# mysch.net
KiCad netlist of a schematic drawn in EAGLE
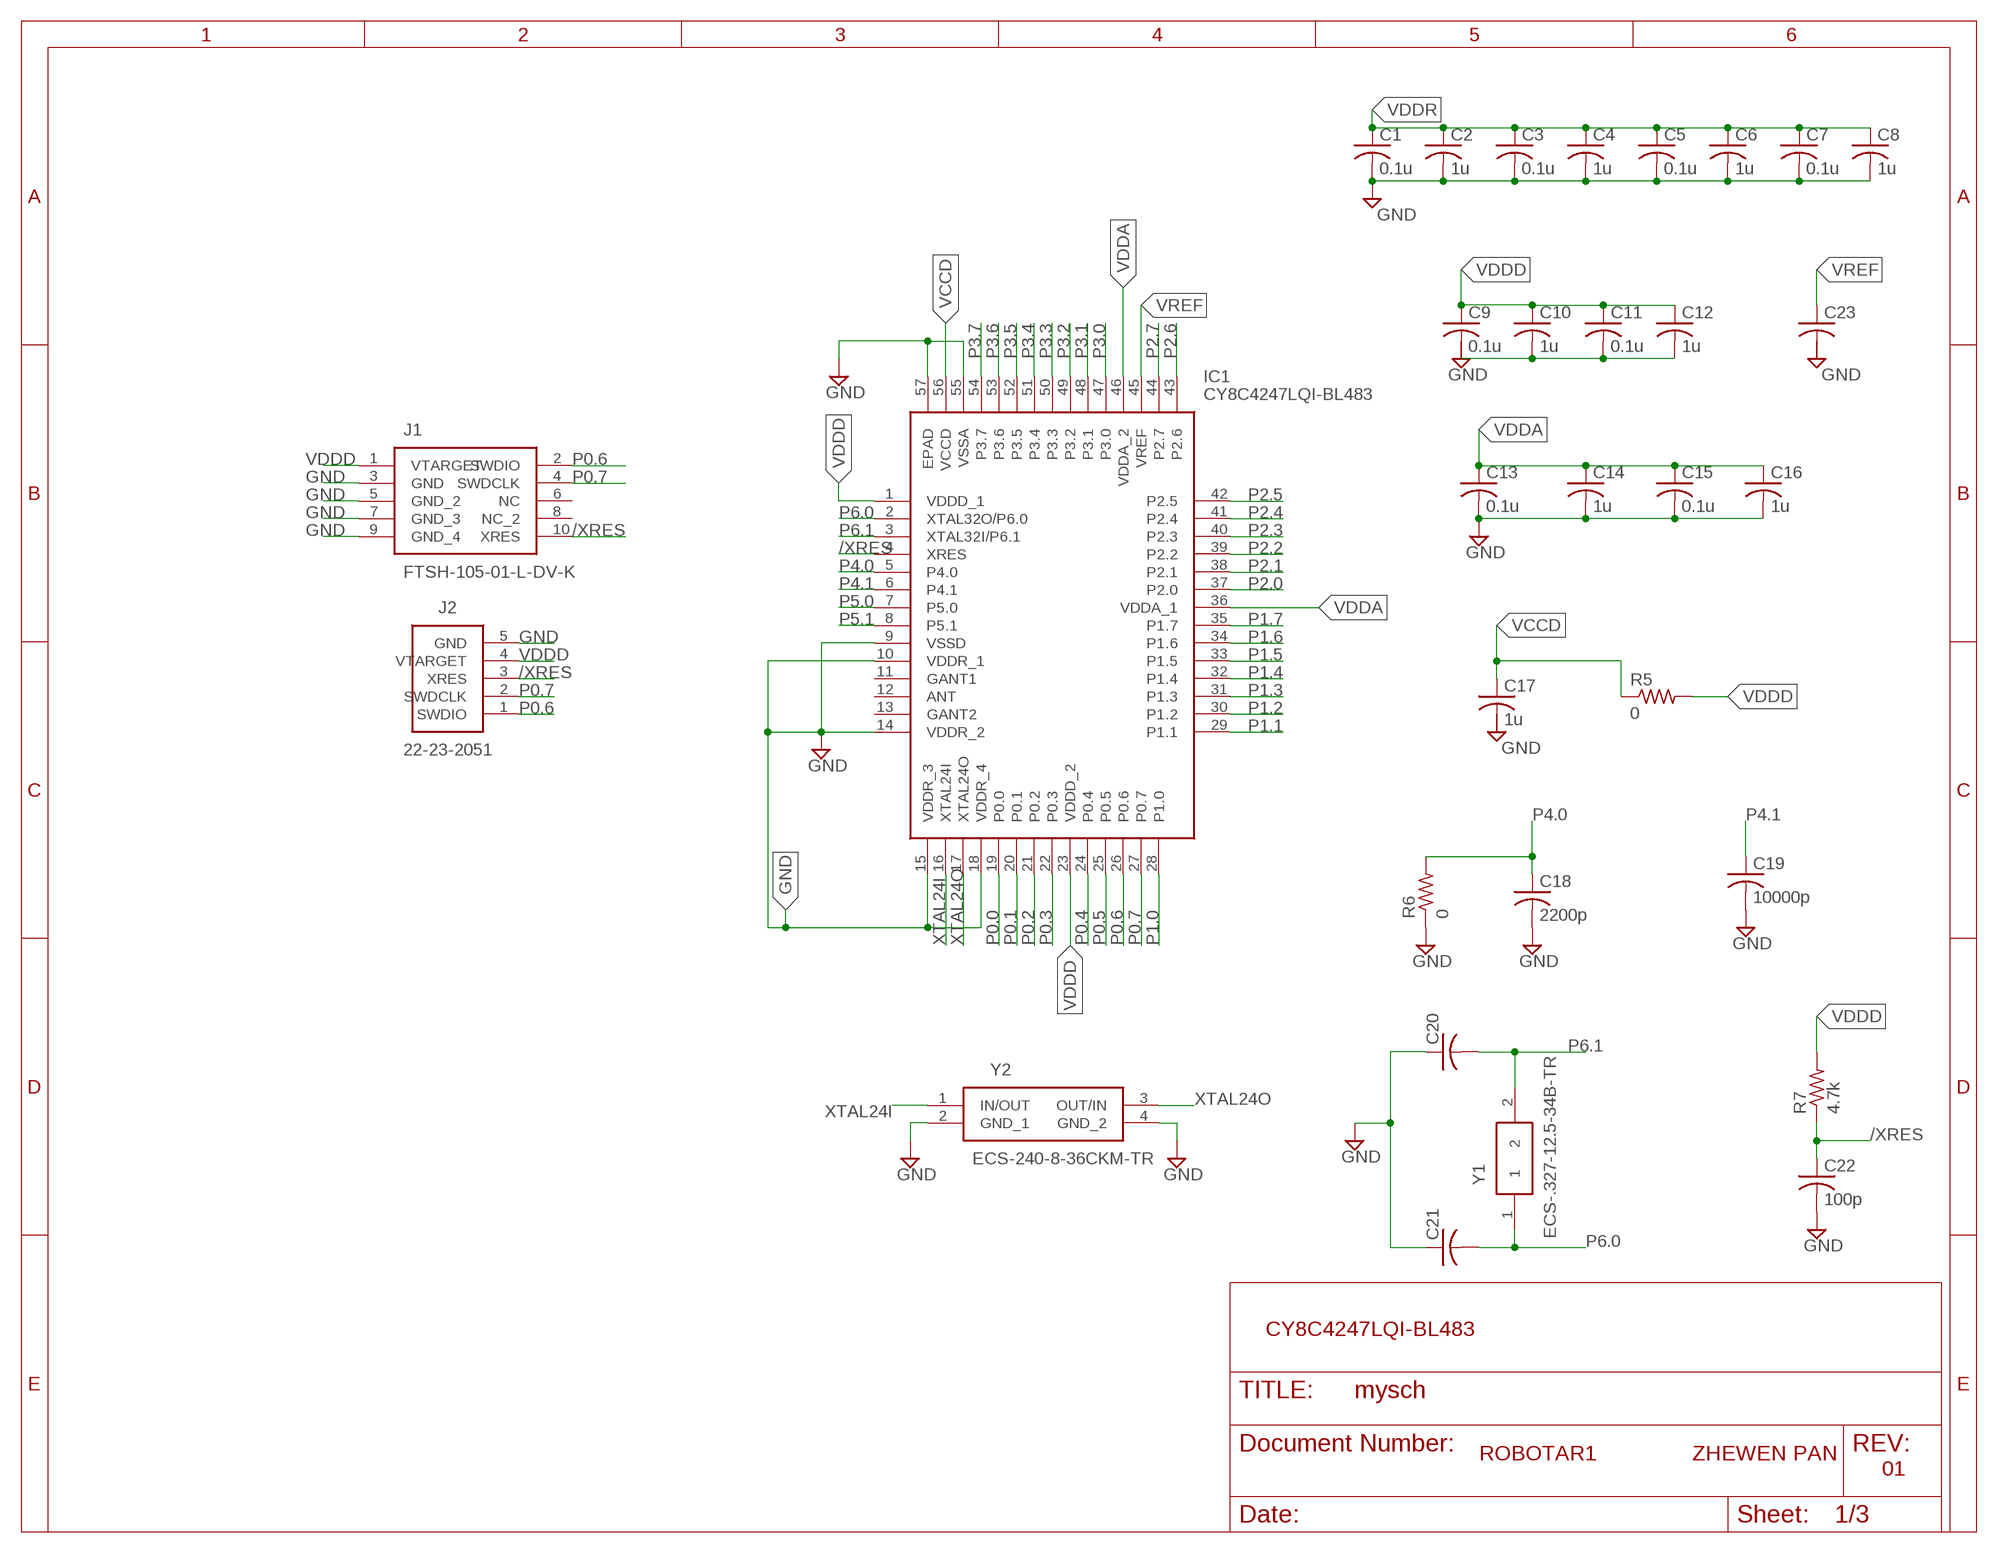
[diagram p0: schematic, sheet 1]
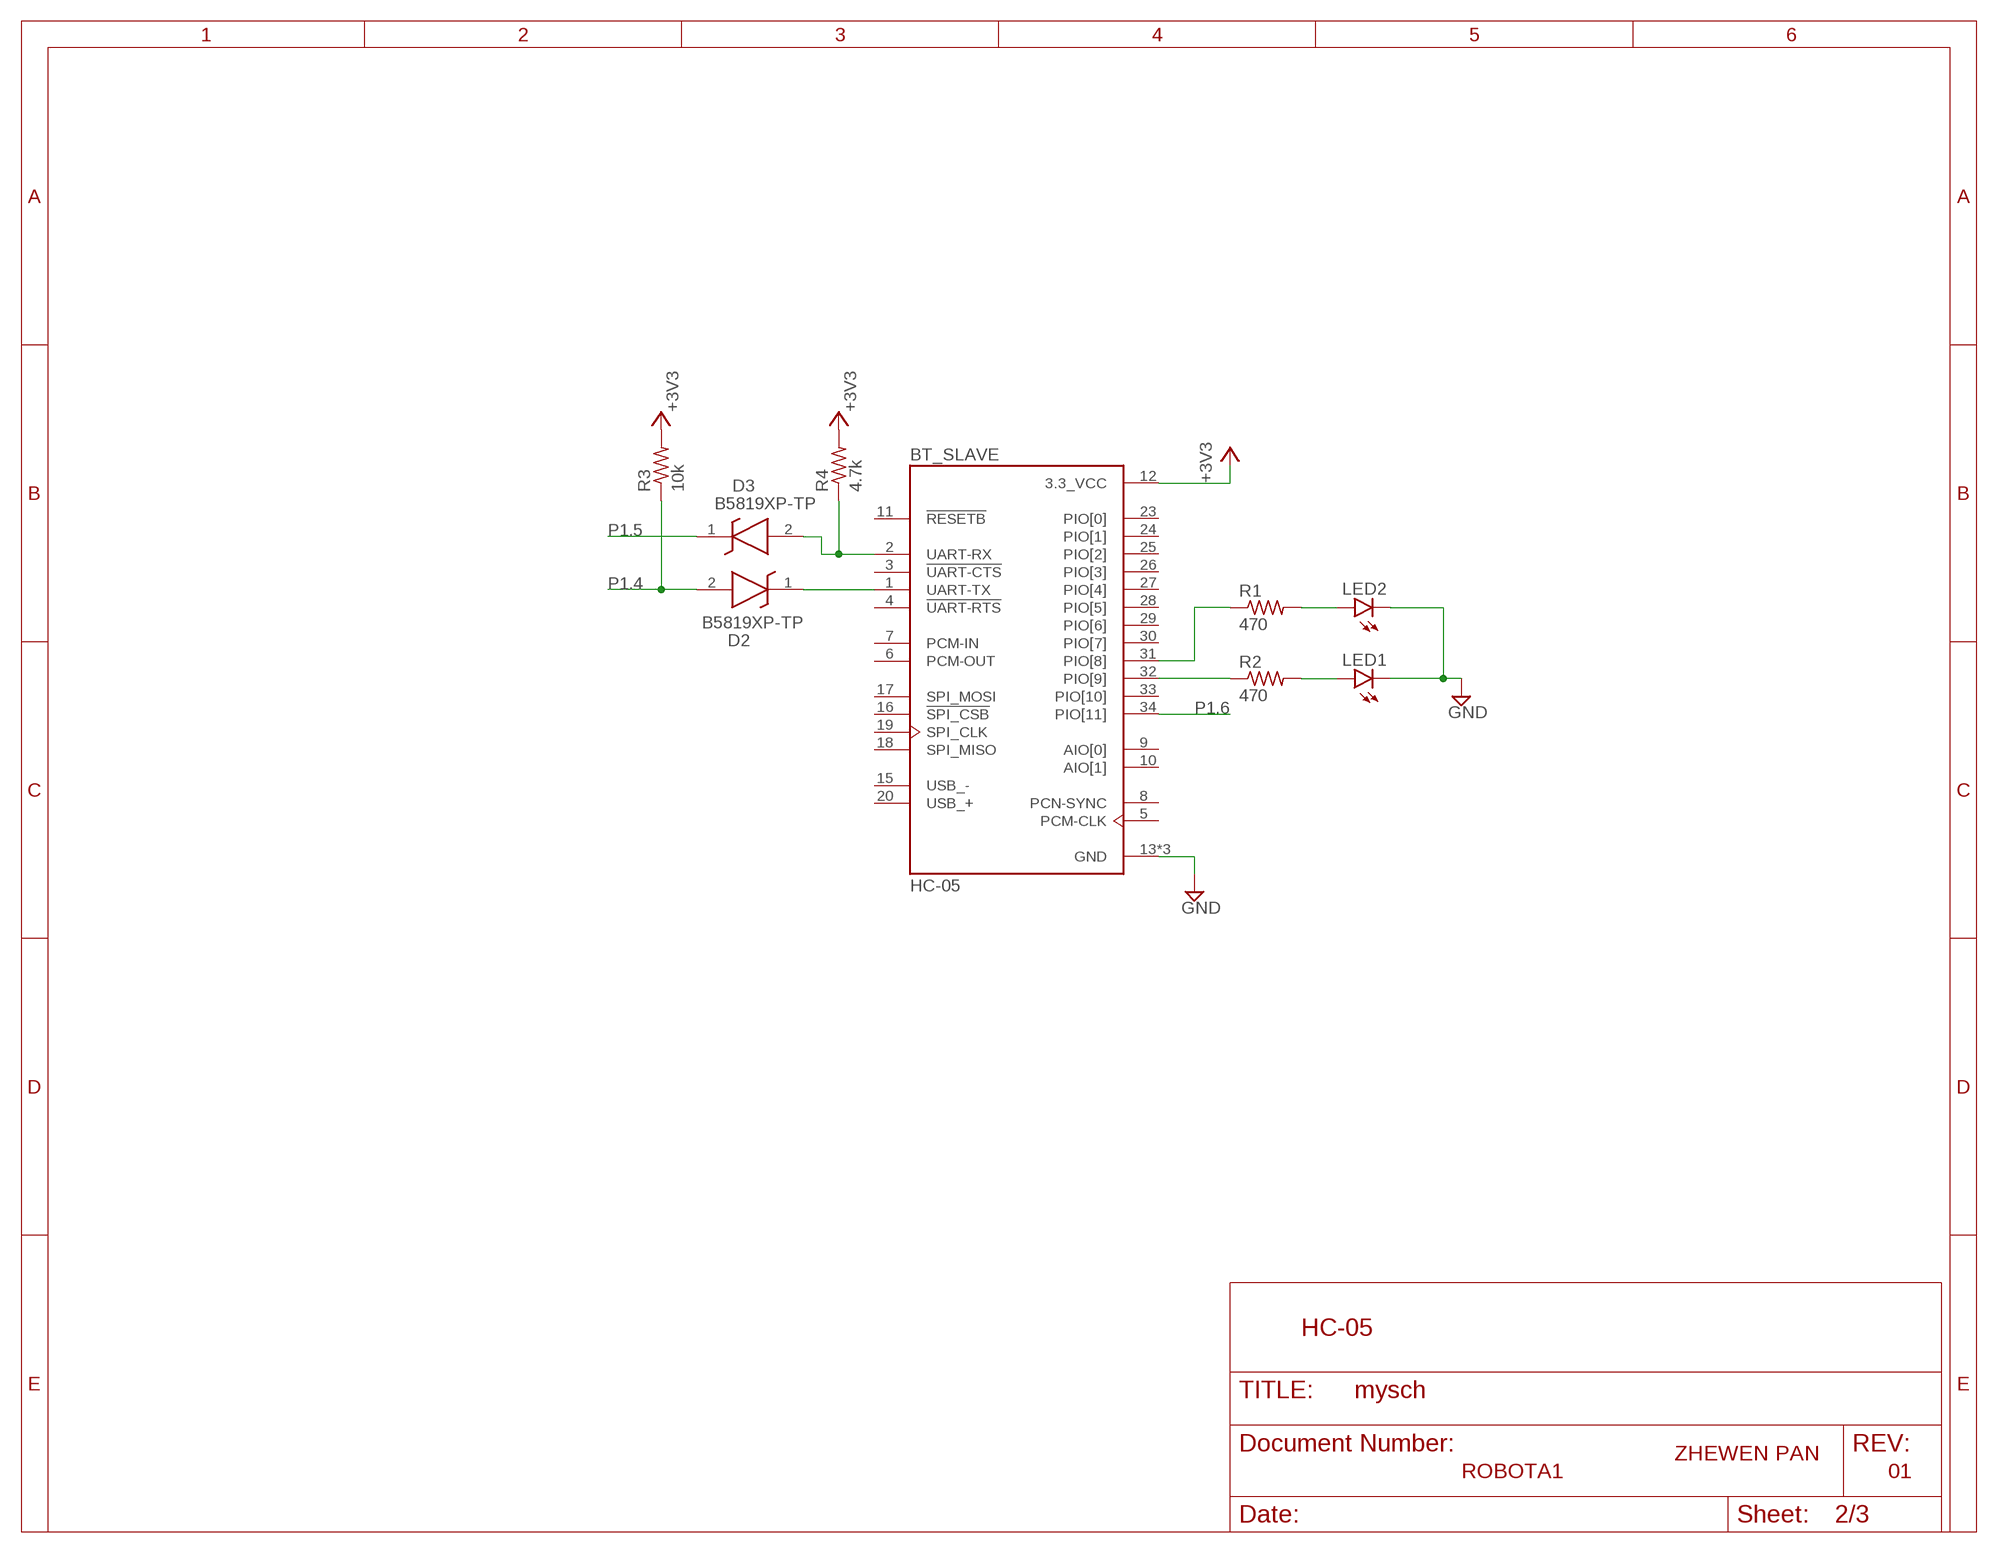
[diagram p1: schematic, sheet 2]
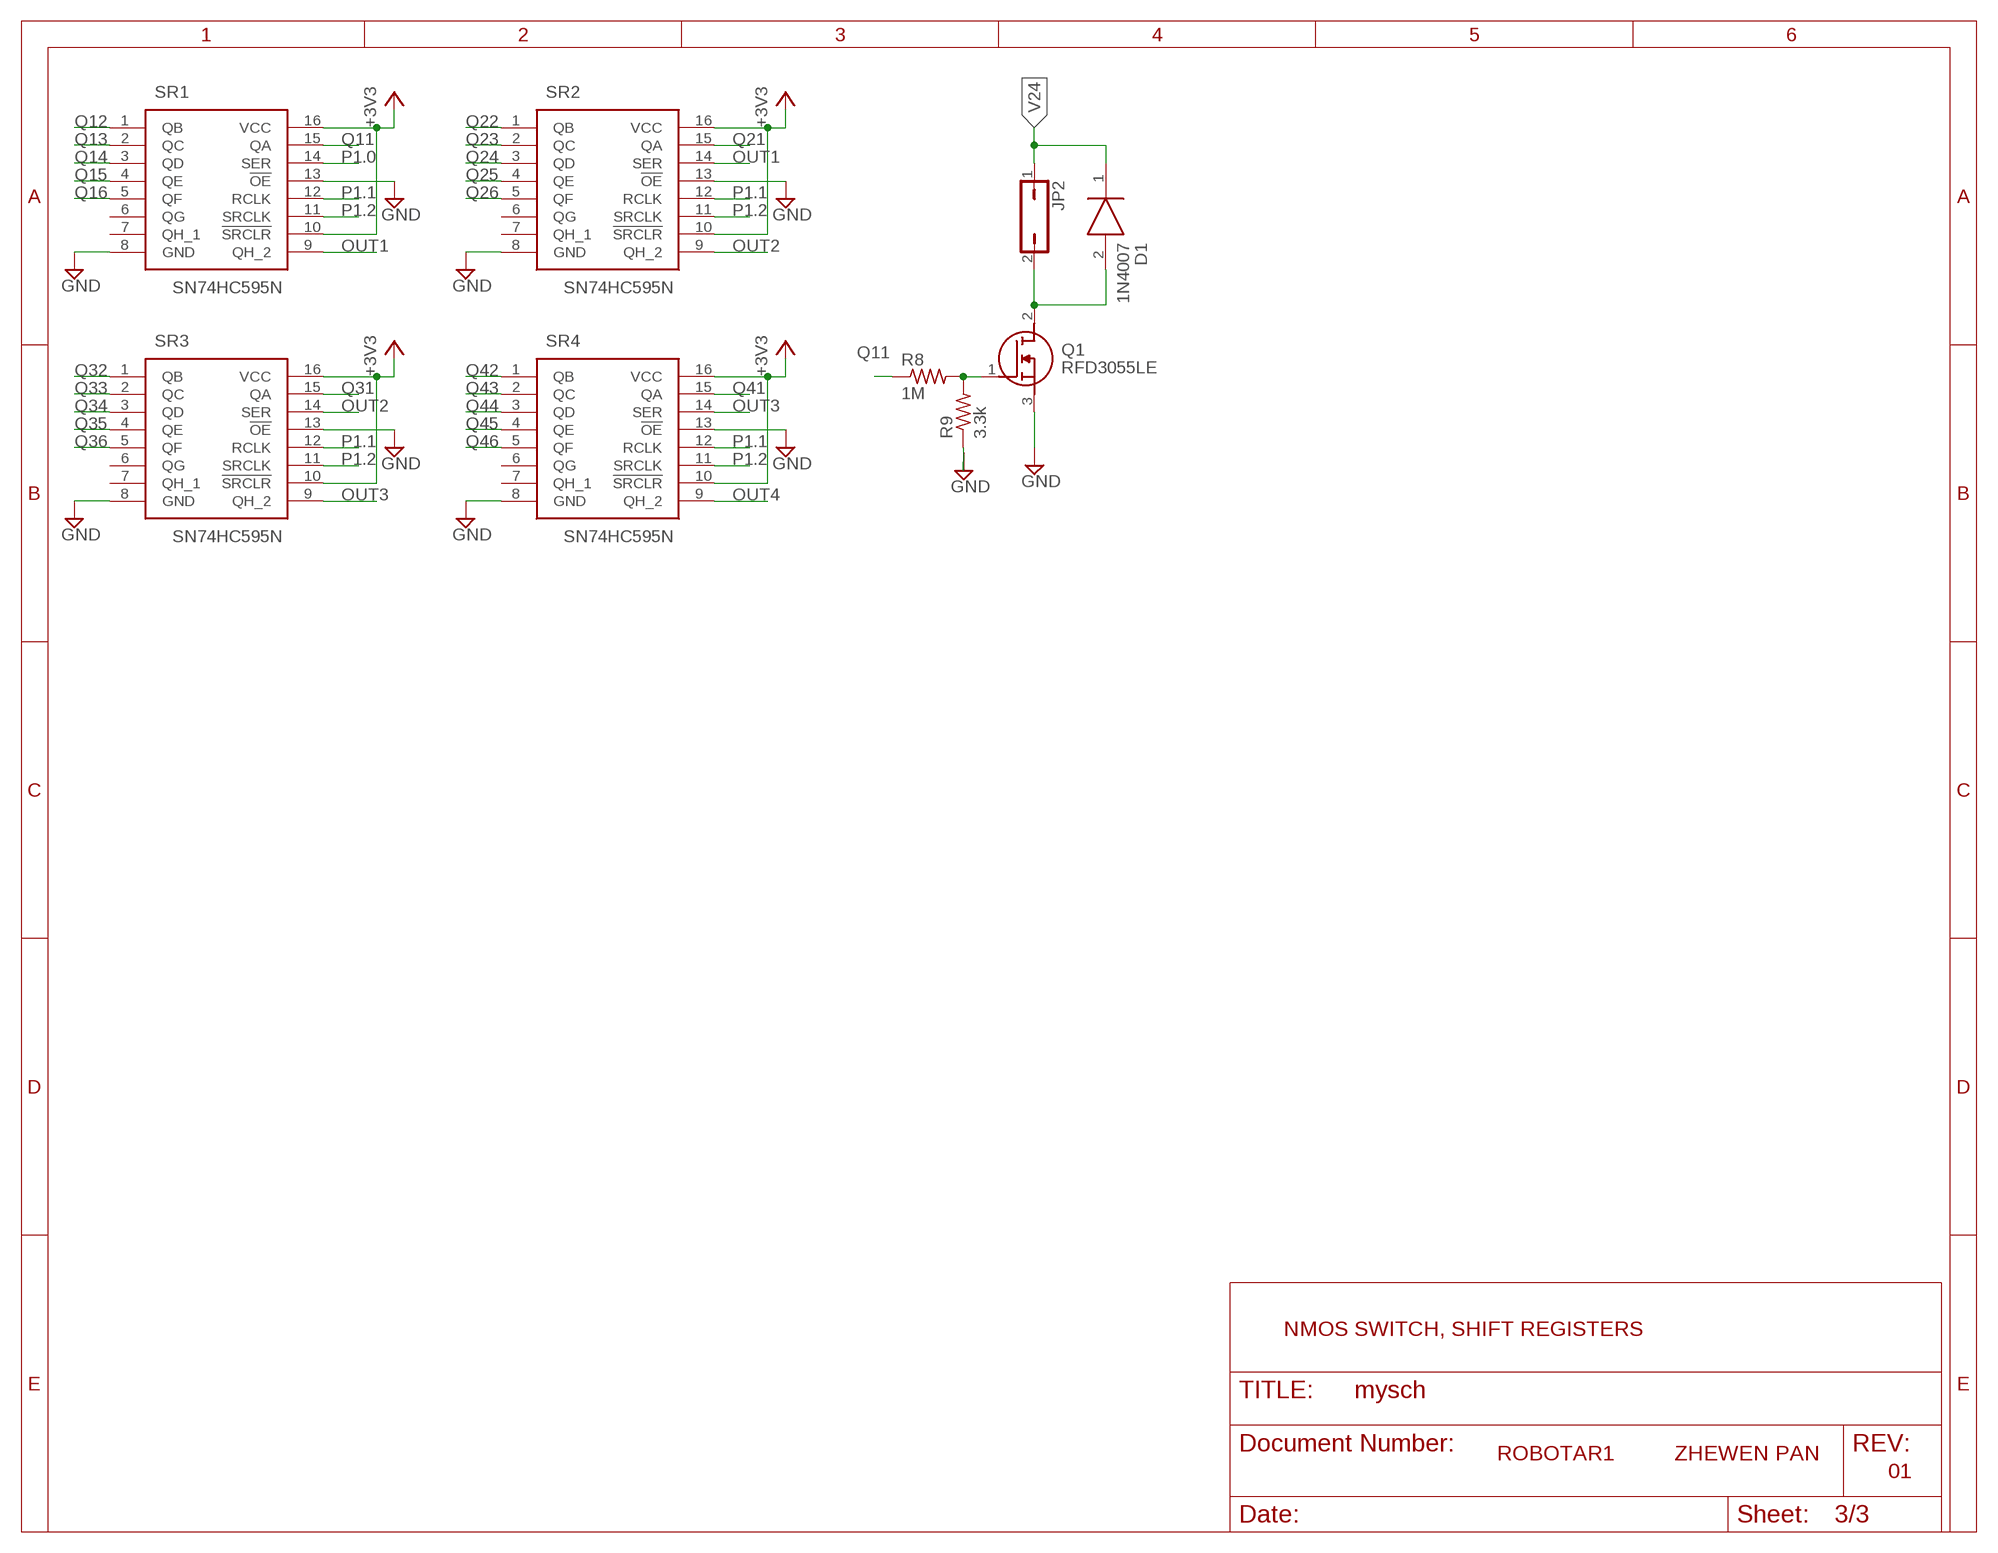
[diagram p2: schematic, sheet 3]

(export (version "E")
  (design (tool "Eeschema 10.0.6"))
  (components
    (comp (ref "BT_SLAVE")
      (value "HC-05")
      (footprint "eagle-import:XCVR_HC-05")
      (fields (field (name "MF") "Texas Instruments") (field (name "SPICEPREFIX") "X"))
      (libsource (lib "eagle-import") (part "HC-05"))
    )
    (comp (ref "D2")
      (value "B5819XP-TP")
      (footprint "eagle-import:B5819XPTP")
      (libsource (lib "eagle-import") (part "B5819XP-TP"))
    )
    (comp (ref "D3")
      (value "B5819XP-TP")
      (footprint "eagle-import:B5819XPTP")
      (libsource (lib "eagle-import") (part "B5819XP-TP"))
    )
    (comp (ref "LED1")
      (value "LEDSML0805")
      (footprint "eagle-import:SML0805")
      (libsource (lib "eagle-import") (part "LEDSML0805"))
    )
    (comp (ref "LED2")
      (value "LEDSML0805")
      (footprint "eagle-import:SML0805")
      (libsource (lib "eagle-import") (part "LEDSML0805"))
    )
    (comp (ref "R1")
      (value "470")
      (footprint "eagle-import:R0805")
      (libsource (lib "eagle-import") (part "R-US_R0805"))
    )
    (comp (ref "R2")
      (value "470")
      (footprint "eagle-import:R0805")
      (libsource (lib "eagle-import") (part "R-US_R0805"))
    )
    (comp (ref "R3")
      (value "10k")
      (footprint "eagle-import:R0805")
      (libsource (lib "eagle-import") (part "R-US_R0805"))
    )
    (comp (ref "R4")
      (value "4.7k")
      (footprint "eagle-import:R0805")
      (libsource (lib "eagle-import") (part "R-US_R0805"))
    )
    (comp (ref "D1")
      (value "1N4007")
      (footprint "eagle-import:DIOAD1410W86L470D235")
      (libsource (lib "eagle-import") (part "1N4007"))
    )
    (comp (ref "JP2")
      (value "JP1Q")
      (footprint "eagle-import:JP1")
      (libsource (lib "eagle-import") (part "JP1Q"))
    )
    (comp (ref "Q1")
      (value "RFD3055LE")
      (footprint "eagle-import:TO229P250X658X985-3P")
      (libsource (lib "eagle-import") (part "RFD3055LE"))
    )
    (comp (ref "R8")
      (value "1M")
      (footprint "eagle-import:R0805")
      (libsource (lib "eagle-import") (part "R-US_R0805"))
    )
    (comp (ref "R9")
      (value "3.3k")
      (footprint "eagle-import:R0805")
      (libsource (lib "eagle-import") (part "R-US_R0805"))
    )
    (comp (ref "SR1")
      (value "SN74HC595N")
      (footprint "eagle-import:DIP794W53P254L1930H508Q16N")
      (fields (field (name "RS_PART_NUMBER") "2175695P"))
      (libsource (lib "eagle-import") (part "SN74HC595N"))
    )
    (comp (ref "SR2")
      (value "SN74HC595N")
      (footprint "eagle-import:DIP794W53P254L1930H508Q16N")
      (fields (field (name "RS_PART_NUMBER") "2175695P"))
      (libsource (lib "eagle-import") (part "SN74HC595N"))
    )
    (comp (ref "SR3")
      (value "SN74HC595N")
      (footprint "eagle-import:DIP794W53P254L1930H508Q16N")
      (fields (field (name "RS_PART_NUMBER") "2175695P"))
      (libsource (lib "eagle-import") (part "SN74HC595N"))
    )
    (comp (ref "SR4")
      (value "SN74HC595N")
      (footprint "eagle-import:DIP794W53P254L1930H508Q16N")
      (fields (field (name "RS_PART_NUMBER") "2175695P"))
      (libsource (lib "eagle-import") (part "SN74HC595N"))
    )
    (comp (ref "C1")
      (value "0.1u")
      (footprint "eagle-import:C0805")
      (libsource (lib "eagle-import") (part "C-USC0805"))
    )
    (comp (ref "C2")
      (value "1u")
      (footprint "eagle-import:C0805")
      (libsource (lib "eagle-import") (part "C-USC0805"))
    )
    (comp (ref "C3")
      (value "0.1u")
      (footprint "eagle-import:C0805")
      (libsource (lib "eagle-import") (part "C-USC0805"))
    )
    (comp (ref "C4")
      (value "1u")
      (footprint "eagle-import:C0805K")
      (libsource (lib "eagle-import") (part "C-USC0805K"))
    )
    (comp (ref "C5")
      (value "0.1u")
      (footprint "eagle-import:C0805")
      (libsource (lib "eagle-import") (part "C-USC0805"))
    )
    (comp (ref "C6")
      (value "1u")
      (footprint "eagle-import:C0805")
      (libsource (lib "eagle-import") (part "C-USC0805"))
    )
    (comp (ref "C7")
      (value "0.1u")
      (footprint "eagle-import:C0805")
      (libsource (lib "eagle-import") (part "C-USC0805"))
    )
    (comp (ref "C8")
      (value "1u")
      (footprint "eagle-import:C0805")
      (libsource (lib "eagle-import") (part "C-USC0805"))
    )
    (comp (ref "C9")
      (value "0.1u")
      (footprint "eagle-import:C0805K")
      (libsource (lib "eagle-import") (part "C-USC0805K"))
    )
    (comp (ref "C10")
      (value "1u")
      (footprint "eagle-import:C0805")
      (libsource (lib "eagle-import") (part "C-USC0805"))
    )
    (comp (ref "C11")
      (value "0.1u")
      (footprint "eagle-import:C0805")
      (libsource (lib "eagle-import") (part "C-USC0805"))
    )
    (comp (ref "C12")
      (value "1u")
      (footprint "eagle-import:C0805")
      (libsource (lib "eagle-import") (part "C-USC0805"))
    )
    (comp (ref "C13")
      (value "0.1u")
      (footprint "eagle-import:C0805")
      (libsource (lib "eagle-import") (part "C-USC0805"))
    )
    (comp (ref "C14")
      (value "1u")
      (footprint "eagle-import:C0805K")
      (libsource (lib "eagle-import") (part "C-USC0805K"))
    )
    (comp (ref "C15")
      (value "0.1u")
      (footprint "eagle-import:C0805K")
      (libsource (lib "eagle-import") (part "C-USC0805K"))
    )
    (comp (ref "C16")
      (value "1u")
      (footprint "eagle-import:C0805K")
      (libsource (lib "eagle-import") (part "C-USC0805K"))
    )
    (comp (ref "C17")
      (value "1u")
      (footprint "eagle-import:C0805")
      (libsource (lib "eagle-import") (part "C-USC0805"))
    )
    (comp (ref "C18")
      (value "2200p")
      (footprint "eagle-import:C0805")
      (libsource (lib "eagle-import") (part "C-USC0805"))
    )
    (comp (ref "C19")
      (value "10000p")
      (footprint "eagle-import:C0805")
      (libsource (lib "eagle-import") (part "C-USC0805"))
    )
    (comp (ref "C20")
      (value "C-USC0805")
      (footprint "eagle-import:C0805")
      (libsource (lib "eagle-import") (part "C-USC0805"))
    )
    (comp (ref "C21")
      (value "C-USC0805")
      (footprint "eagle-import:C0805")
      (libsource (lib "eagle-import") (part "C-USC0805"))
    )
    (comp (ref "C22")
      (value "100p")
      (footprint "eagle-import:C0805")
      (libsource (lib "eagle-import") (part "C-USC0805"))
    )
    (comp (ref "C23")
      (value "C-USC0805")
      (footprint "eagle-import:C0805")
      (libsource (lib "eagle-import") (part "C-USC0805"))
    )
    (comp (ref "IC1")
      (value "CY8C4247LQI-BL483")
      (footprint "eagle-import:QFN40P700X700X60-57N")
      (fields (field (name "RS_PART_NUMBER") "1242964P"))
      (libsource (lib "eagle-import") (part "CY8C4247LQI-BL483"))
    )
    (comp (ref "J1")
      (value "FTSH-105-01-L-DV-K")
      (footprint "eagle-import:FTSH-105-01-L-DV-K")
      (fields (field (name "RS_PART_NUMBER") "1592332"))
      (libsource (lib "eagle-import") (part "FTSH-105-01-L-DV-K"))
    )
    (comp (ref "J2")
      (value "22-23-2051")
      (footprint "eagle-import:HDRV5W64P0X254_1X5_1255X635X81")
      (fields (field (name "RS_PART_NUMBER") "1888757"))
      (libsource (lib "eagle-import") (part "22-23-2051"))
    )
    (comp (ref "R5")
      (value "0")
      (footprint "eagle-import:R0805")
      (libsource (lib "eagle-import") (part "R-US_R0805"))
    )
    (comp (ref "R6")
      (value "0")
      (footprint "eagle-import:R0805")
      (libsource (lib "eagle-import") (part "R-US_R0805"))
    )
    (comp (ref "R7")
      (value "4.7k")
      (footprint "eagle-import:R0805")
      (libsource (lib "eagle-import") (part "R-US_R0805"))
    )
    (comp (ref "Y1")
      (value "ECS-.327-12.5-34B-TR")
      (footprint "eagle-import:ECX-31B")
      (libsource (lib "eagle-import") (part "ECS-.327-12.5-34B-TR"))
    )
    (comp (ref "Y2")
      (value "ECS-240-8-36CKM-TR")
      (footprint "eagle-import:ECS240836QAESTR")
      (libsource (lib "eagle-import") (part "ECS-240-8-36CKM-TR"))
    )
  )
  (nets
    (net (code "1") (name "+3V3") (class "Default")
      (node (ref "BT_SLAVE") (pin "12") (pinfunction "3.3_VCC_12") (pintype "power_in"))
      (node (ref "R3") (pin "2") (pinfunction "2_2") (pintype "passive"))
      (node (ref "R4") (pin "2") (pinfunction "2_2") (pintype "passive"))
      (node (ref "SR1") (pin "10") (pinfunction "~{SRCLR}_10") (pintype "bidirectional"))
      (node (ref "SR1") (pin "16") (pinfunction "VCC_16") (pintype "power_in"))
      (node (ref "SR2") (pin "10") (pinfunction "~{SRCLR}_10") (pintype "bidirectional"))
      (node (ref "SR2") (pin "16") (pinfunction "VCC_16") (pintype "power_in"))
      (node (ref "SR3") (pin "10") (pinfunction "~{SRCLR}_10") (pintype "bidirectional"))
      (node (ref "SR3") (pin "16") (pinfunction "VCC_16") (pintype "power_in"))
      (node (ref "SR4") (pin "10") (pinfunction "~{SRCLR}_10") (pintype "bidirectional"))
      (node (ref "SR4") (pin "16") (pinfunction "VCC_16") (pintype "power_in"))
    )
    (net (code "2") (name "GND") (class "Default")
      (node (ref "BT_SLAVE") (pin "13") (pinfunction "GND_13") (pintype "power_in"))
      (node (ref "BT_SLAVE") (pin "21") (pinfunction "GND_21") (pintype "power_in"))
      (node (ref "BT_SLAVE") (pin "22") (pinfunction "GND_22") (pintype "power_in"))
      (node (ref "C1") (pin "2") (pinfunction "2_2") (pintype "passive"))
      (node (ref "C13") (pin "2") (pinfunction "2_2") (pintype "passive"))
      (node (ref "C14") (pin "2") (pinfunction "2_2") (pintype "passive"))
      (node (ref "C15") (pin "2") (pinfunction "2_2") (pintype "passive"))
      (node (ref "C16") (pin "2") (pinfunction "2_2") (pintype "passive"))
      (node (ref "C18") (pin "2") (pinfunction "2_2") (pintype "passive"))
      (node (ref "C19") (pin "2") (pinfunction "2_2") (pintype "passive"))
      (node (ref "C2") (pin "2") (pinfunction "2_2") (pintype "passive"))
      (node (ref "C20") (pin "1") (pinfunction "1_1") (pintype "passive"))
      (node (ref "C21") (pin "1") (pinfunction "1_1") (pintype "passive"))
      (node (ref "C22") (pin "2") (pinfunction "2_2") (pintype "passive"))
      (node (ref "C3") (pin "2") (pinfunction "2_2") (pintype "passive"))
      (node (ref "C4") (pin "2") (pinfunction "2_2") (pintype "passive"))
      (node (ref "C5") (pin "2") (pinfunction "2_2") (pintype "passive"))
      (node (ref "C6") (pin "2") (pinfunction "2_2") (pintype "passive"))
      (node (ref "C7") (pin "2") (pinfunction "2_2") (pintype "passive"))
      (node (ref "C8") (pin "2") (pinfunction "2_2") (pintype "passive"))
      (node (ref "IC1") (pin "10") (pinfunction "VDDR_1_10") (pintype "bidirectional"))
      (node (ref "IC1") (pin "14") (pinfunction "VDDR_2_14") (pintype "bidirectional"))
      (node (ref "IC1") (pin "15") (pinfunction "VDDR_3_15") (pintype "bidirectional"))
      (node (ref "IC1") (pin "18") (pinfunction "VDDR_4_18") (pintype "bidirectional"))
      (node (ref "IC1") (pin "55") (pinfunction "VSSA_55") (pintype "bidirectional"))
      (node (ref "IC1") (pin "57") (pinfunction "EPAD_57") (pintype "bidirectional"))
      (node (ref "IC1") (pin "9") (pinfunction "VSSD_9") (pintype "bidirectional"))
      (node (ref "J1") (pin "3") (pinfunction "GND_3") (pintype "bidirectional"))
      (node (ref "J1") (pin "5") (pinfunction "GND_2_5") (pintype "bidirectional"))
      (node (ref "J1") (pin "7") (pinfunction "GND_3_7") (pintype "bidirectional"))
      (node (ref "J1") (pin "9") (pinfunction "GND_4_9") (pintype "bidirectional"))
      (node (ref "J2") (pin "5") (pinfunction "GND_5") (pintype "bidirectional"))
      (node (ref "LED1") (pin "C") (pinfunction "C_C") (pintype "passive"))
      (node (ref "LED2") (pin "C") (pinfunction "C_C") (pintype "passive"))
      (node (ref "Q1") (pin "3") (pinfunction "S_3") (pintype "bidirectional"))
      (node (ref "R6") (pin "1") (pinfunction "1_1") (pintype "passive"))
      (node (ref "R9") (pin "1") (pinfunction "1_1") (pintype "passive"))
      (node (ref "SR1") (pin "13") (pinfunction "~{OE}_13") (pintype "bidirectional"))
      (node (ref "SR1") (pin "8") (pinfunction "GND_8") (pintype "power_in"))
      (node (ref "SR2") (pin "13") (pinfunction "~{OE}_13") (pintype "bidirectional"))
      (node (ref "SR2") (pin "8") (pinfunction "GND_8") (pintype "power_in"))
      (node (ref "SR3") (pin "13") (pinfunction "~{OE}_13") (pintype "bidirectional"))
      (node (ref "SR3") (pin "8") (pinfunction "GND_8") (pintype "power_in"))
      (node (ref "SR4") (pin "13") (pinfunction "~{OE}_13") (pintype "bidirectional"))
      (node (ref "SR4") (pin "8") (pinfunction "GND_8") (pintype "power_in"))
      (node (ref "Y2") (pin "2") (pinfunction "GND_1_2") (pintype "bidirectional"))
      (node (ref "Y2") (pin "4") (pinfunction "GND_2_4") (pintype "bidirectional"))
    )
    (net (code "3") (name "Net-(BT_SLAVE-PIO[8])") (class "Default")
      (node (ref "BT_SLAVE") (pin "31") (pinfunction "PIO[8]_31") (pintype "bidirectional"))
      (node (ref "R1") (pin "1") (pinfunction "1_1") (pintype "passive"))
    )
    (net (code "4") (name "Net-(BT_SLAVE-PIO[9])") (class "Default")
      (node (ref "BT_SLAVE") (pin "32") (pinfunction "PIO[9]_32") (pintype "bidirectional"))
      (node (ref "R2") (pin "1") (pinfunction "1_1") (pintype "passive"))
    )
    (net (code "5") (name "Net-(BT_SLAVE-UART-RX)") (class "Default")
      (node (ref "BT_SLAVE") (pin "2") (pinfunction "UART-RX_2") (pintype "input"))
      (node (ref "D3") (pin "2") (pinfunction "+_2") (pintype "bidirectional"))
      (node (ref "R4") (pin "1") (pinfunction "1_1") (pintype "passive"))
    )
    (net (code "6") (name "Net-(BT_SLAVE-UART-TX)") (class "Default")
      (node (ref "BT_SLAVE") (pin "1") (pinfunction "UART-TX_1") (pintype "output"))
      (node (ref "D2") (pin "1") (pinfunction "-_1") (pintype "bidirectional"))
    )
    (net (code "7") (name "Net-(C10-Pad2)") (class "Default")
      (node (ref "C10") (pin "2") (pinfunction "2_2") (pintype "passive"))
      (node (ref "C11") (pin "2") (pinfunction "2_2") (pintype "passive"))
      (node (ref "C12") (pin "2") (pinfunction "2_2") (pintype "passive"))
      (node (ref "C9") (pin "2") (pinfunction "2_2") (pintype "passive"))
    )
    (net (code "8") (name "Net-(D1-A)") (class "Default")
      (node (ref "D1") (pin "2") (pinfunction "A_2") (pintype "bidirectional"))
      (node (ref "JP2") (pin "2") (pinfunction "2_2") (pintype "passive"))
      (node (ref "Q1") (pin "2") (pinfunction "D_2") (pintype "bidirectional"))
    )
    (net (code "9") (name "Net-(LED1-PadA)") (class "Default")
      (node (ref "LED1") (pin "A") (pinfunction "A_A") (pintype "passive"))
      (node (ref "R2") (pin "2") (pinfunction "2_2") (pintype "passive"))
    )
    (net (code "10") (name "Net-(LED2-PadA)") (class "Default")
      (node (ref "LED2") (pin "A") (pinfunction "A_A") (pintype "passive"))
      (node (ref "R1") (pin "2") (pinfunction "2_2") (pintype "passive"))
    )
    (net (code "11") (name "Net-(Q1-G)") (class "Default")
      (node (ref "Q1") (pin "1") (pinfunction "G_1") (pintype "bidirectional"))
      (node (ref "R8") (pin "2") (pinfunction "2_2") (pintype "passive"))
      (node (ref "R9") (pin "2") (pinfunction "2_2") (pintype "passive"))
    )
    (net (code "12") (name "OUT1") (class "Default")
      (node (ref "SR1") (pin "9") (pinfunction "QH_2_9") (pintype "bidirectional"))
      (node (ref "SR2") (pin "14") (pinfunction "SER_14") (pintype "bidirectional"))
    )
    (net (code "13") (name "OUT2") (class "Default")
      (node (ref "SR2") (pin "9") (pinfunction "QH_2_9") (pintype "bidirectional"))
      (node (ref "SR3") (pin "14") (pinfunction "SER_14") (pintype "bidirectional"))
    )
    (net (code "14") (name "OUT3") (class "Default")
      (node (ref "SR3") (pin "9") (pinfunction "QH_2_9") (pintype "bidirectional"))
      (node (ref "SR4") (pin "14") (pinfunction "SER_14") (pintype "bidirectional"))
    )
    (net (code "15") (name "OUT4") (class "Default")
      (node (ref "SR4") (pin "9") (pinfunction "QH_2_9") (pintype "bidirectional"))
    )
    (net (code "16") (name "P0.0") (class "Default")
      (node (ref "IC1") (pin "19") (pinfunction "P0.0_19") (pintype "bidirectional"))
    )
    (net (code "17") (name "P0.1") (class "Default")
      (node (ref "IC1") (pin "20") (pinfunction "P0.1_20") (pintype "bidirectional"))
    )
    (net (code "18") (name "P0.2") (class "Default")
      (node (ref "IC1") (pin "21") (pinfunction "P0.2_21") (pintype "bidirectional"))
    )
    (net (code "19") (name "P0.3") (class "Default")
      (node (ref "IC1") (pin "22") (pinfunction "P0.3_22") (pintype "bidirectional"))
    )
    (net (code "20") (name "P0.4") (class "Default")
      (node (ref "IC1") (pin "24") (pinfunction "P0.4_24") (pintype "bidirectional"))
    )
    (net (code "21") (name "P0.5") (class "Default")
      (node (ref "IC1") (pin "25") (pinfunction "P0.5_25") (pintype "bidirectional"))
    )
    (net (code "22") (name "P0.6") (class "Default")
      (node (ref "IC1") (pin "26") (pinfunction "P0.6_26") (pintype "bidirectional"))
      (node (ref "J1") (pin "2") (pinfunction "SWDIO_2") (pintype "bidirectional"))
      (node (ref "J2") (pin "1") (pinfunction "SWDIO_1") (pintype "bidirectional"))
    )
    (net (code "23") (name "P0.7") (class "Default")
      (node (ref "IC1") (pin "27") (pinfunction "P0.7_27") (pintype "bidirectional"))
      (node (ref "J1") (pin "4") (pinfunction "SWDCLK_4") (pintype "bidirectional"))
      (node (ref "J2") (pin "2") (pinfunction "SWDCLK_2") (pintype "bidirectional"))
    )
    (net (code "24") (name "P1.0") (class "Default")
      (node (ref "IC1") (pin "28") (pinfunction "P1.0_28") (pintype "bidirectional"))
      (node (ref "SR1") (pin "14") (pinfunction "SER_14") (pintype "bidirectional"))
    )
    (net (code "25") (name "P1.1") (class "Default")
      (node (ref "IC1") (pin "29") (pinfunction "P1.1_29") (pintype "bidirectional"))
      (node (ref "SR1") (pin "12") (pinfunction "RCLK_12") (pintype "input"))
      (node (ref "SR2") (pin "12") (pinfunction "RCLK_12") (pintype "input"))
      (node (ref "SR3") (pin "12") (pinfunction "RCLK_12") (pintype "input"))
      (node (ref "SR4") (pin "12") (pinfunction "RCLK_12") (pintype "input"))
    )
    (net (code "26") (name "P1.2") (class "Default")
      (node (ref "IC1") (pin "30") (pinfunction "P1.2_30") (pintype "bidirectional"))
      (node (ref "SR1") (pin "11") (pinfunction "SRCLK_11") (pintype "input"))
      (node (ref "SR2") (pin "11") (pinfunction "SRCLK_11") (pintype "input"))
      (node (ref "SR3") (pin "11") (pinfunction "SRCLK_11") (pintype "input"))
      (node (ref "SR4") (pin "11") (pinfunction "SRCLK_11") (pintype "input"))
    )
    (net (code "27") (name "P1.3") (class "Default")
      (node (ref "IC1") (pin "31") (pinfunction "P1.3_31") (pintype "bidirectional"))
    )
    (net (code "28") (name "P1.4") (class "Default")
      (node (ref "D2") (pin "2") (pinfunction "+_2") (pintype "bidirectional"))
      (node (ref "IC1") (pin "32") (pinfunction "P1.4_32") (pintype "bidirectional"))
      (node (ref "R3") (pin "1") (pinfunction "1_1") (pintype "passive"))
    )
    (net (code "29") (name "P1.5") (class "Default")
      (node (ref "D3") (pin "1") (pinfunction "-_1") (pintype "bidirectional"))
      (node (ref "IC1") (pin "33") (pinfunction "P1.5_33") (pintype "bidirectional"))
    )
    (net (code "30") (name "P1.6") (class "Default")
      (node (ref "BT_SLAVE") (pin "34") (pinfunction "PIO[11]_34") (pintype "bidirectional"))
      (node (ref "IC1") (pin "34") (pinfunction "P1.6_34") (pintype "bidirectional"))
    )
    (net (code "31") (name "P1.7") (class "Default")
      (node (ref "IC1") (pin "35") (pinfunction "P1.7_35") (pintype "bidirectional"))
    )
    (net (code "32") (name "P2.0") (class "Default")
      (node (ref "IC1") (pin "37") (pinfunction "P2.0_37") (pintype "bidirectional"))
    )
    (net (code "33") (name "P2.1") (class "Default")
      (node (ref "IC1") (pin "38") (pinfunction "P2.1_38") (pintype "bidirectional"))
    )
    (net (code "34") (name "P2.2") (class "Default")
      (node (ref "IC1") (pin "39") (pinfunction "P2.2_39") (pintype "bidirectional"))
    )
    (net (code "35") (name "P2.3") (class "Default")
      (node (ref "IC1") (pin "40") (pinfunction "P2.3_40") (pintype "bidirectional"))
    )
    (net (code "36") (name "P2.4") (class "Default")
      (node (ref "IC1") (pin "41") (pinfunction "P2.4_41") (pintype "bidirectional"))
    )
    (net (code "37") (name "P2.5") (class "Default")
      (node (ref "IC1") (pin "42") (pinfunction "P2.5_42") (pintype "bidirectional"))
    )
    (net (code "38") (name "P2.6") (class "Default")
      (node (ref "IC1") (pin "43") (pinfunction "P2.6_43") (pintype "bidirectional"))
    )
    (net (code "39") (name "P2.7") (class "Default")
      (node (ref "IC1") (pin "44") (pinfunction "P2.7_44") (pintype "bidirectional"))
    )
    (net (code "40") (name "P3.0") (class "Default")
      (node (ref "IC1") (pin "47") (pinfunction "P3.0_47") (pintype "bidirectional"))
    )
    (net (code "41") (name "P3.1") (class "Default")
      (node (ref "IC1") (pin "48") (pinfunction "P3.1_48") (pintype "bidirectional"))
    )
    (net (code "42") (name "P3.2") (class "Default")
      (node (ref "IC1") (pin "49") (pinfunction "P3.2_49") (pintype "bidirectional"))
    )
    (net (code "43") (name "P3.3") (class "Default")
      (node (ref "IC1") (pin "50") (pinfunction "P3.3_50") (pintype "bidirectional"))
    )
    (net (code "44") (name "P3.4") (class "Default")
      (node (ref "IC1") (pin "51") (pinfunction "P3.4_51") (pintype "bidirectional"))
    )
    (net (code "45") (name "P3.5") (class "Default")
      (node (ref "IC1") (pin "52") (pinfunction "P3.5_52") (pintype "bidirectional"))
    )
    (net (code "46") (name "P3.6") (class "Default")
      (node (ref "IC1") (pin "53") (pinfunction "P3.6_53") (pintype "bidirectional"))
    )
    (net (code "47") (name "P3.7") (class "Default")
      (node (ref "IC1") (pin "54") (pinfunction "P3.7_54") (pintype "bidirectional"))
    )
    (net (code "48") (name "P4.0") (class "Default")
      (node (ref "C18") (pin "1") (pinfunction "1_1") (pintype "passive"))
      (node (ref "IC1") (pin "5") (pinfunction "P4.0_5") (pintype "bidirectional"))
      (node (ref "R6") (pin "2") (pinfunction "2_2") (pintype "passive"))
    )
    (net (code "49") (name "P4.1") (class "Default")
      (node (ref "C19") (pin "1") (pinfunction "1_1") (pintype "passive"))
      (node (ref "IC1") (pin "6") (pinfunction "P4.1_6") (pintype "bidirectional"))
    )
    (net (code "50") (name "P5.0") (class "Default")
      (node (ref "IC1") (pin "7") (pinfunction "P5.0_7") (pintype "bidirectional"))
    )
    (net (code "51") (name "P5.1") (class "Default")
      (node (ref "IC1") (pin "8") (pinfunction "P5.1_8") (pintype "bidirectional"))
    )
    (net (code "52") (name "P6.0") (class "Default")
      (node (ref "C21") (pin "2") (pinfunction "2_2") (pintype "passive"))
      (node (ref "IC1") (pin "2") (pinfunction "XTAL32O/P6.0_2") (pintype "bidirectional"))
      (node (ref "Y1") (pin "1") (pinfunction "1_1") (pintype "bidirectional"))
    )
    (net (code "53") (name "P6.1") (class "Default")
      (node (ref "C20") (pin "2") (pinfunction "2_2") (pintype "passive"))
      (node (ref "IC1") (pin "3") (pinfunction "XTAL32I/P6.1_3") (pintype "bidirectional"))
      (node (ref "Y1") (pin "2") (pinfunction "2_2") (pintype "bidirectional"))
    )
    (net (code "54") (name "Q11") (class "Default")
      (node (ref "R8") (pin "1") (pinfunction "1_1") (pintype "passive"))
      (node (ref "SR1") (pin "15") (pinfunction "QA_15") (pintype "bidirectional"))
    )
    (net (code "55") (name "Q12") (class "Default")
      (node (ref "SR1") (pin "1") (pinfunction "QB_1") (pintype "bidirectional"))
    )
    (net (code "56") (name "Q13") (class "Default")
      (node (ref "SR1") (pin "2") (pinfunction "QC_2") (pintype "bidirectional"))
    )
    (net (code "57") (name "Q14") (class "Default")
      (node (ref "SR1") (pin "3") (pinfunction "QD_3") (pintype "bidirectional"))
    )
    (net (code "58") (name "Q15") (class "Default")
      (node (ref "SR1") (pin "4") (pinfunction "QE_4") (pintype "bidirectional"))
    )
    (net (code "59") (name "Q16") (class "Default")
      (node (ref "SR1") (pin "5") (pinfunction "QF_5") (pintype "bidirectional"))
    )
    (net (code "60") (name "Q21") (class "Default")
      (node (ref "SR2") (pin "15") (pinfunction "QA_15") (pintype "bidirectional"))
    )
    (net (code "61") (name "Q22") (class "Default")
      (node (ref "SR2") (pin "1") (pinfunction "QB_1") (pintype "bidirectional"))
    )
    (net (code "62") (name "Q23") (class "Default")
      (node (ref "SR2") (pin "2") (pinfunction "QC_2") (pintype "bidirectional"))
    )
    (net (code "63") (name "Q24") (class "Default")
      (node (ref "SR2") (pin "3") (pinfunction "QD_3") (pintype "bidirectional"))
    )
    (net (code "64") (name "Q25") (class "Default")
      (node (ref "SR2") (pin "4") (pinfunction "QE_4") (pintype "bidirectional"))
    )
    (net (code "65") (name "Q26") (class "Default")
      (node (ref "SR2") (pin "5") (pinfunction "QF_5") (pintype "bidirectional"))
    )
    (net (code "66") (name "Q31") (class "Default")
      (node (ref "SR3") (pin "15") (pinfunction "QA_15") (pintype "bidirectional"))
    )
    (net (code "67") (name "Q32") (class "Default")
      (node (ref "SR3") (pin "1") (pinfunction "QB_1") (pintype "bidirectional"))
    )
    (net (code "68") (name "Q33") (class "Default")
      (node (ref "SR3") (pin "2") (pinfunction "QC_2") (pintype "bidirectional"))
    )
    (net (code "69") (name "Q34") (class "Default")
      (node (ref "SR3") (pin "3") (pinfunction "QD_3") (pintype "bidirectional"))
    )
    (net (code "70") (name "Q35") (class "Default")
      (node (ref "SR3") (pin "4") (pinfunction "QE_4") (pintype "bidirectional"))
    )
    (net (code "71") (name "Q36") (class "Default")
      (node (ref "SR3") (pin "5") (pinfunction "QF_5") (pintype "bidirectional"))
    )
    (net (code "72") (name "Q41") (class "Default")
      (node (ref "SR4") (pin "15") (pinfunction "QA_15") (pintype "bidirectional"))
    )
    (net (code "73") (name "Q42") (class "Default")
      (node (ref "SR4") (pin "1") (pinfunction "QB_1") (pintype "bidirectional"))
    )
    (net (code "74") (name "Q43") (class "Default")
      (node (ref "SR4") (pin "2") (pinfunction "QC_2") (pintype "bidirectional"))
    )
    (net (code "75") (name "Q44") (class "Default")
      (node (ref "SR4") (pin "3") (pinfunction "QD_3") (pintype "bidirectional"))
    )
    (net (code "76") (name "Q45") (class "Default")
      (node (ref "SR4") (pin "4") (pinfunction "QE_4") (pintype "bidirectional"))
    )
    (net (code "77") (name "Q46") (class "Default")
      (node (ref "SR4") (pin "5") (pinfunction "QF_5") (pintype "bidirectional"))
    )
    (net (code "78") (name "V24") (class "Default")
      (node (ref "D1") (pin "1") (pinfunction "K_1") (pintype "bidirectional"))
      (node (ref "JP2") (pin "1") (pinfunction "1_1") (pintype "passive"))
    )
    (net (code "79") (name "VCCD") (class "Default")
      (node (ref "C17") (pin "1") (pinfunction "1_1") (pintype "passive"))
      (node (ref "IC1") (pin "56") (pinfunction "VCCD_56") (pintype "bidirectional"))
      (node (ref "R5") (pin "1") (pinfunction "1_1") (pintype "passive"))
    )
    (net (code "80") (name "VDDA") (class "Default")
      (node (ref "C13") (pin "1") (pinfunction "1_1") (pintype "passive"))
      (node (ref "C14") (pin "1") (pinfunction "1_1") (pintype "passive"))
      (node (ref "C15") (pin "1") (pinfunction "1_1") (pintype "passive"))
      (node (ref "C16") (pin "1") (pinfunction "1_1") (pintype "passive"))
      (node (ref "IC1") (pin "36") (pinfunction "VDDA_1_36") (pintype "bidirectional"))
      (node (ref "IC1") (pin "46") (pinfunction "VDDA_2_46") (pintype "bidirectional"))
    )
    (net (code "81") (name "VDDD") (class "Default")
      (node (ref "C10") (pin "1") (pinfunction "1_1") (pintype "passive"))
      (node (ref "C11") (pin "1") (pinfunction "1_1") (pintype "passive"))
      (node (ref "C12") (pin "1") (pinfunction "1_1") (pintype "passive"))
      (node (ref "C9") (pin "1") (pinfunction "1_1") (pintype "passive"))
      (node (ref "IC1") (pin "1") (pinfunction "VDDD_1_1") (pintype "bidirectional"))
      (node (ref "IC1") (pin "23") (pinfunction "VDDD_2_23") (pintype "bidirectional"))
      (node (ref "J1") (pin "1") (pinfunction "VTARGET_1") (pintype "bidirectional"))
      (node (ref "J2") (pin "4") (pinfunction "VTARGET_4") (pintype "bidirectional"))
      (node (ref "R5") (pin "2") (pinfunction "2_2") (pintype "passive"))
      (node (ref "R7") (pin "2") (pinfunction "2_2") (pintype "passive"))
    )
    (net (code "82") (name "VDDR") (class "Default")
      (node (ref "C1") (pin "1") (pinfunction "1_1") (pintype "passive"))
      (node (ref "C2") (pin "1") (pinfunction "1_1") (pintype "passive"))
      (node (ref "C3") (pin "1") (pinfunction "1_1") (pintype "passive"))
      (node (ref "C4") (pin "1") (pinfunction "1_1") (pintype "passive"))
      (node (ref "C5") (pin "1") (pinfunction "1_1") (pintype "passive"))
      (node (ref "C6") (pin "1") (pinfunction "1_1") (pintype "passive"))
      (node (ref "C7") (pin "1") (pinfunction "1_1") (pintype "passive"))
      (node (ref "C8") (pin "1") (pinfunction "1_1") (pintype "passive"))
    )
    (net (code "83") (name "VREF") (class "Default")
      (node (ref "C23") (pin "1") (pinfunction "1_1") (pintype "passive"))
      (node (ref "IC1") (pin "45") (pinfunction "VREF_45") (pintype "bidirectional"))
    )
    (net (code "84") (name "XTAL24I") (class "Default")
      (node (ref "IC1") (pin "16") (pinfunction "XTAL24I_16") (pintype "bidirectional"))
      (node (ref "Y2") (pin "1") (pinfunction "IN/OUT_1") (pintype "bidirectional"))
    )
    (net (code "85") (name "XTAL24O") (class "Default")
      (node (ref "IC1") (pin "17") (pinfunction "XTAL24O_17") (pintype "bidirectional"))
      (node (ref "Y2") (pin "3") (pinfunction "OUT/IN_3") (pintype "bidirectional"))
    )
    (net (code "86") (name "unconnected-(BT_SLAVE-AIO[0]-Pad9)") (class "Default")
      (node (ref "BT_SLAVE") (pin "9") (pinfunction "AIO[0]_9") (pintype "bidirectional"))
    )
    (net (code "87") (name "unconnected-(BT_SLAVE-AIO[1]-Pad10)") (class "Default")
      (node (ref "BT_SLAVE") (pin "10") (pinfunction "AIO[1]_10") (pintype "bidirectional"))
    )
    (net (code "88") (name "unconnected-(BT_SLAVE-PCM-CLK-Pad5)") (class "Default")
      (node (ref "BT_SLAVE") (pin "5") (pinfunction "PCM-CLK_5") (pintype "bidirectional"))
    )
    (net (code "89") (name "unconnected-(BT_SLAVE-PCM-IN-Pad7)") (class "Default")
      (node (ref "BT_SLAVE") (pin "7") (pinfunction "PCM-IN_7") (pintype "input"))
    )
    (net (code "90") (name "unconnected-(BT_SLAVE-PCM-OUT-Pad6)") (class "Default")
      (node (ref "BT_SLAVE") (pin "6") (pinfunction "PCM-OUT_6") (pintype "output"))
    )
    (net (code "91") (name "unconnected-(BT_SLAVE-PCN-SYNC-Pad8)") (class "Default")
      (node (ref "BT_SLAVE") (pin "8") (pinfunction "PCN-SYNC_8") (pintype "bidirectional"))
    )
    (net (code "92") (name "unconnected-(BT_SLAVE-PIO[0]-Pad23)") (class "Default")
      (node (ref "BT_SLAVE") (pin "23") (pinfunction "PIO[0]_23") (pintype "bidirectional"))
    )
    (net (code "93") (name "unconnected-(BT_SLAVE-PIO[1]-Pad24)") (class "Default")
      (node (ref "BT_SLAVE") (pin "24") (pinfunction "PIO[1]_24") (pintype "bidirectional"))
    )
    (net (code "94") (name "unconnected-(BT_SLAVE-PIO[2]-Pad25)") (class "Default")
      (node (ref "BT_SLAVE") (pin "25") (pinfunction "PIO[2]_25") (pintype "bidirectional"))
    )
    (net (code "95") (name "unconnected-(BT_SLAVE-PIO[3]-Pad26)") (class "Default")
      (node (ref "BT_SLAVE") (pin "26") (pinfunction "PIO[3]_26") (pintype "bidirectional"))
    )
    (net (code "96") (name "unconnected-(BT_SLAVE-PIO[4]-Pad27)") (class "Default")
      (node (ref "BT_SLAVE") (pin "27") (pinfunction "PIO[4]_27") (pintype "bidirectional"))
    )
    (net (code "97") (name "unconnected-(BT_SLAVE-PIO[5]-Pad28)") (class "Default")
      (node (ref "BT_SLAVE") (pin "28") (pinfunction "PIO[5]_28") (pintype "bidirectional"))
    )
    (net (code "98") (name "unconnected-(BT_SLAVE-PIO[6]-Pad29)") (class "Default")
      (node (ref "BT_SLAVE") (pin "29") (pinfunction "PIO[6]_29") (pintype "bidirectional"))
    )
    (net (code "99") (name "unconnected-(BT_SLAVE-PIO[7]-Pad30)") (class "Default")
      (node (ref "BT_SLAVE") (pin "30") (pinfunction "PIO[7]_30") (pintype "bidirectional"))
    )
    (net (code "100") (name "unconnected-(BT_SLAVE-PIO[10]-Pad33)") (class "Default")
      (node (ref "BT_SLAVE") (pin "33") (pinfunction "PIO[10]_33") (pintype "bidirectional"))
    )
    (net (code "101") (name "unconnected-(BT_SLAVE-SPI_CLK-Pad19)") (class "Default")
      (node (ref "BT_SLAVE") (pin "19") (pinfunction "SPI_CLK_19") (pintype "input"))
    )
    (net (code "102") (name "unconnected-(BT_SLAVE-SPI_MISO-Pad18)") (class "Default")
      (node (ref "BT_SLAVE") (pin "18") (pinfunction "SPI_MISO_18") (pintype "output"))
    )
    (net (code "103") (name "unconnected-(BT_SLAVE-SPI_MOSI-Pad17)") (class "Default")
      (node (ref "BT_SLAVE") (pin "17") (pinfunction "SPI_MOSI_17") (pintype "input"))
    )
    (net (code "104") (name "unconnected-(BT_SLAVE-USB_+-Pad20)") (class "Default")
      (node (ref "BT_SLAVE") (pin "20") (pinfunction "USB_+_20") (pintype "bidirectional"))
    )
    (net (code "105") (name "unconnected-(BT_SLAVE-USB_--Pad15)") (class "Default")
      (node (ref "BT_SLAVE") (pin "15") (pinfunction "USB_-_15") (pintype "bidirectional"))
    )
    (net (code "106") (name "unconnected-(BT_SLAVE-~{RESETB}-Pad11)") (class "Default")
      (node (ref "BT_SLAVE") (pin "11") (pinfunction "~{RESETB}_11") (pintype "input"))
    )
    (net (code "107") (name "unconnected-(BT_SLAVE-~{SPI_CSB}-Pad16)") (class "Default")
      (node (ref "BT_SLAVE") (pin "16") (pinfunction "~{SPI_CSB}_16") (pintype "input"))
    )
    (net (code "108") (name "unconnected-(BT_SLAVE-~{UART-CTS}-Pad3)") (class "Default")
      (node (ref "BT_SLAVE") (pin "3") (pinfunction "~{UART-CTS}_3") (pintype "input"))
    )
    (net (code "109") (name "unconnected-(BT_SLAVE-~{UART-RTS}-Pad4)") (class "Default")
      (node (ref "BT_SLAVE") (pin "4") (pinfunction "~{UART-RTS}_4") (pintype "output"))
    )
    (net (code "110") (name "unconnected-(C17-Pad2)") (class "Default")
      (node (ref "C17") (pin "2") (pinfunction "2_2") (pintype "passive"))
    )
    (net (code "111") (name "unconnected-(C23-Pad2)") (class "Default")
      (node (ref "C23") (pin "2") (pinfunction "2_2") (pintype "passive"))
    )
    (net (code "112") (name "unconnected-(IC1-ANT-Pad12)") (class "Default")
      (node (ref "IC1") (pin "12") (pinfunction "ANT_12") (pintype "bidirectional"))
    )
    (net (code "113") (name "unconnected-(IC1-GANT1-Pad11)") (class "Default")
      (node (ref "IC1") (pin "11") (pinfunction "GANT1_11") (pintype "bidirectional"))
    )
    (net (code "114") (name "unconnected-(IC1-GANT2-Pad13)") (class "Default")
      (node (ref "IC1") (pin "13") (pinfunction "GANT2_13") (pintype "bidirectional"))
    )
    (net (code "115") (name "unconnected-(J1-NC-Pad6)") (class "Default")
      (node (ref "J1") (pin "6") (pinfunction "NC_6") (pintype "bidirectional"))
    )
    (net (code "116") (name "unconnected-(J1-NC_2-Pad8)") (class "Default")
      (node (ref "J1") (pin "8") (pinfunction "NC_2_8") (pintype "bidirectional"))
    )
    (net (code "117") (name "unconnected-(SR1-QG-Pad6)") (class "Default")
      (node (ref "SR1") (pin "6") (pinfunction "QG_6") (pintype "bidirectional"))
    )
    (net (code "118") (name "unconnected-(SR1-QH_1-Pad7)") (class "Default")
      (node (ref "SR1") (pin "7") (pinfunction "QH_1_7") (pintype "bidirectional"))
    )
    (net (code "119") (name "unconnected-(SR2-QG-Pad6)") (class "Default")
      (node (ref "SR2") (pin "6") (pinfunction "QG_6") (pintype "bidirectional"))
    )
    (net (code "120") (name "unconnected-(SR2-QH_1-Pad7)") (class "Default")
      (node (ref "SR2") (pin "7") (pinfunction "QH_1_7") (pintype "bidirectional"))
    )
    (net (code "121") (name "unconnected-(SR3-QG-Pad6)") (class "Default")
      (node (ref "SR3") (pin "6") (pinfunction "QG_6") (pintype "bidirectional"))
    )
    (net (code "122") (name "unconnected-(SR3-QH_1-Pad7)") (class "Default")
      (node (ref "SR3") (pin "7") (pinfunction "QH_1_7") (pintype "bidirectional"))
    )
    (net (code "123") (name "unconnected-(SR4-QG-Pad6)") (class "Default")
      (node (ref "SR4") (pin "6") (pinfunction "QG_6") (pintype "bidirectional"))
    )
    (net (code "124") (name "unconnected-(SR4-QH_1-Pad7)") (class "Default")
      (node (ref "SR4") (pin "7") (pinfunction "QH_1_7") (pintype "bidirectional"))
    )
    (net (code "125") (name "{slash}XRES") (class "Default")
      (node (ref "C22") (pin "1") (pinfunction "1_1") (pintype "passive"))
      (node (ref "IC1") (pin "4") (pinfunction "XRES_4") (pintype "bidirectional"))
      (node (ref "J1") (pin "10") (pinfunction "XRES_10") (pintype "bidirectional"))
      (node (ref "J2") (pin "3") (pinfunction "XRES_3") (pintype "bidirectional"))
      (node (ref "R7") (pin "1") (pinfunction "1_1") (pintype "passive"))
    )
  )
)
